# Puzzle_4-Digit_Display_v2_0.net
KiCad netlist of a schematic drawn in EAGLE
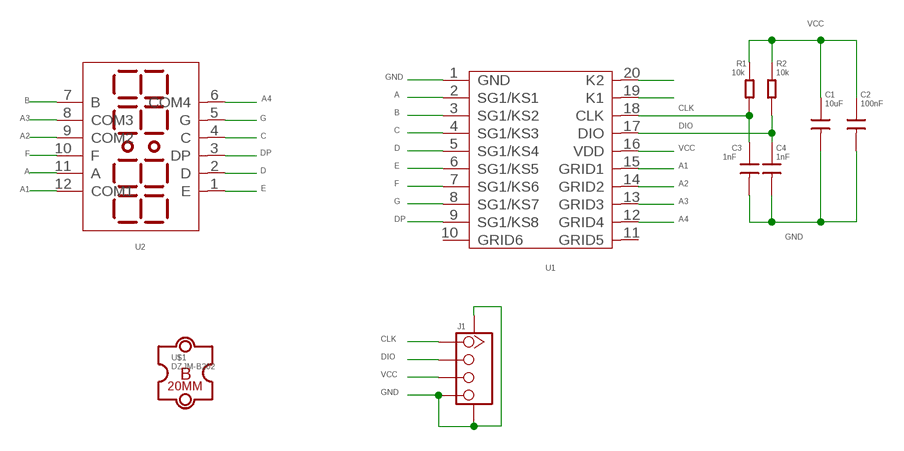
[diagram p0: schematic, sheet 1]

(export (version "E")
  (design (tool "Eeschema 10.0.6"))
  (components
    (comp (ref "C1")
      (value "10uF")
      (footprint "eagle-import:0603")
      (libsource (lib "eagle-import") (part "C-0603"))
    )
    (comp (ref "C2")
      (value "100nF")
      (footprint "eagle-import:0603")
      (libsource (lib "eagle-import") (part "C-0603"))
    )
    (comp (ref "C3")
      (value "1nF")
      (footprint "eagle-import:0603")
      (libsource (lib "eagle-import") (part "C-0603"))
    )
    (comp (ref "C4")
      (value "1nF")
      (footprint "eagle-import:0603")
      (libsource (lib "eagle-import") (part "C-0603"))
    )
    (comp (ref "J1")
      (value "TWIG-4P-2.0-SMD-FEMALE-REINFORCE'90D'")
      (footprint "eagle-import:4P-SMD-2.0-90D")
      (libsource (lib "eagle-import") (part "TWIG-4P-2.0-SMD-FEMALE-REINFORCE'90D'"))
    )
    (comp (ref "R1")
      (value "10k")
      (footprint "eagle-import:0603")
      (libsource (lib "eagle-import") (part "R-0603"))
    )
    (comp (ref "R2")
      (value "10k")
      (footprint "eagle-import:0603")
      (libsource (lib "eagle-import") (part "R-0603"))
    )
    (comp (ref "U$1")
      (value "DZJM-B202")
      (footprint "eagle-import:DZJM-B20-2P")
      (libsource (lib "eagle-import") (part "DZJM-B202"))
    )
    (comp (ref "U1")
      (value "TM1637")
      (footprint "eagle-import:SOP20-10.45")
      (libsource (lib "eagle-import") (part "TM1637"))
    )
    (comp (ref "U2")
      (value "LED-4-BETY-7-SEG")
      (footprint "eagle-import:7-4-BYTE-SEG-2.54-30X14X7.3H")
      (libsource (lib "eagle-import") (part "LED-4-BETY-7-SEG"))
    )
  )
  (nets
    (net (code "1") (name "/A") (class "Default")
      (node (ref "U1") (pin "2") (pinfunction "SG1/KS1_2") (pintype "bidirectional"))
      (node (ref "U2") (pin "11") (pinfunction "A_11") (pintype "bidirectional"))
    )
    (net (code "2") (name "/A1") (class "Default")
      (node (ref "U1") (pin "15") (pinfunction "GRID1_15") (pintype "bidirectional"))
      (node (ref "U2") (pin "12") (pinfunction "COM1_12") (pintype "bidirectional"))
    )
    (net (code "3") (name "/A2") (class "Default")
      (node (ref "U1") (pin "14") (pinfunction "GRID2_14") (pintype "bidirectional"))
      (node (ref "U2") (pin "9") (pinfunction "COM2_9") (pintype "bidirectional"))
    )
    (net (code "4") (name "/A3") (class "Default")
      (node (ref "U1") (pin "13") (pinfunction "GRID3_13") (pintype "bidirectional"))
      (node (ref "U2") (pin "8") (pinfunction "COM3_8") (pintype "bidirectional"))
    )
    (net (code "5") (name "/A4") (class "Default")
      (node (ref "U1") (pin "12") (pinfunction "GRID4_12") (pintype "bidirectional"))
      (node (ref "U2") (pin "6") (pinfunction "COM4_6") (pintype "bidirectional"))
    )
    (net (code "6") (name "/B") (class "Default")
      (node (ref "U1") (pin "3") (pinfunction "SG1/KS2_3") (pintype "bidirectional"))
      (node (ref "U2") (pin "7") (pinfunction "B_7") (pintype "bidirectional"))
    )
    (net (code "7") (name "/C") (class "Default")
      (node (ref "U1") (pin "4") (pinfunction "SG1/KS3_4") (pintype "bidirectional"))
      (node (ref "U2") (pin "4") (pinfunction "C_4") (pintype "bidirectional"))
    )
    (net (code "8") (name "/CLK") (class "Default")
      (node (ref "C3") (pin "1") (pinfunction "1_1") (pintype "passive"))
      (node (ref "J1") (pin "1") (pinfunction "1_1") (pintype "bidirectional"))
      (node (ref "R1") (pin "2") (pinfunction "2_2") (pintype "passive"))
      (node (ref "U1") (pin "18") (pinfunction "CLK_18") (pintype "bidirectional"))
    )
    (net (code "9") (name "/D") (class "Default")
      (node (ref "U1") (pin "5") (pinfunction "SG1/KS4_5") (pintype "bidirectional"))
      (node (ref "U2") (pin "2") (pinfunction "D_2") (pintype "bidirectional"))
    )
    (net (code "10") (name "/DIO") (class "Default")
      (node (ref "C4") (pin "1") (pinfunction "1_1") (pintype "passive"))
      (node (ref "J1") (pin "2") (pinfunction "2_2") (pintype "bidirectional"))
      (node (ref "R2") (pin "2") (pinfunction "2_2") (pintype "passive"))
      (node (ref "U1") (pin "17") (pinfunction "DIO_17") (pintype "bidirectional"))
    )
    (net (code "11") (name "/DP") (class "Default")
      (node (ref "U1") (pin "9") (pinfunction "SG1/KS8_9") (pintype "bidirectional"))
      (node (ref "U2") (pin "3") (pinfunction "DP_3") (pintype "bidirectional"))
    )
    (net (code "12") (name "/E") (class "Default")
      (node (ref "U1") (pin "6") (pinfunction "SG1/KS5_6") (pintype "bidirectional"))
      (node (ref "U2") (pin "1") (pinfunction "E_1") (pintype "bidirectional"))
    )
    (net (code "13") (name "/F") (class "Default")
      (node (ref "U1") (pin "7") (pinfunction "SG1/KS6_7") (pintype "bidirectional"))
      (node (ref "U2") (pin "10") (pinfunction "F_10") (pintype "bidirectional"))
    )
    (net (code "14") (name "/G") (class "Default")
      (node (ref "U1") (pin "8") (pinfunction "SG1/KS7_8") (pintype "bidirectional"))
      (node (ref "U2") (pin "5") (pinfunction "G_5") (pintype "bidirectional"))
    )
    (net (code "15") (name "/GND") (class "Default")
      (node (ref "C1") (pin "2") (pinfunction "2_2") (pintype "passive"))
      (node (ref "C2") (pin "2") (pinfunction "2_2") (pintype "passive"))
      (node (ref "C3") (pin "2") (pinfunction "2_2") (pintype "passive"))
      (node (ref "C4") (pin "2") (pinfunction "2_2") (pintype "passive"))
      (node (ref "J1") (pin "4") (pinfunction "4_4") (pintype "bidirectional"))
      (node (ref "J1") (pin "SS1") (pinfunction "SS1_SS1") (pintype "bidirectional"))
      (node (ref "J1") (pin "SS2") (pinfunction "SS2_SS2") (pintype "bidirectional"))
      (node (ref "U1") (pin "1") (pinfunction "GND_1") (pintype "bidirectional"))
    )
    (net (code "16") (name "/VCC") (class "Default")
      (node (ref "C1") (pin "1") (pinfunction "1_1") (pintype "passive"))
      (node (ref "C2") (pin "1") (pinfunction "1_1") (pintype "passive"))
      (node (ref "J1") (pin "3") (pinfunction "3_3") (pintype "bidirectional"))
      (node (ref "R1") (pin "1") (pinfunction "1_1") (pintype "passive"))
      (node (ref "R2") (pin "1") (pinfunction "1_1") (pintype "passive"))
      (node (ref "U1") (pin "16") (pinfunction "VDD_16") (pintype "bidirectional"))
    )
    (net (code "17") (name "unconnected-(U1-GRID5-Pad11)") (class "Default")
      (node (ref "U1") (pin "11") (pinfunction "GRID5_11") (pintype "bidirectional"))
    )
    (net (code "18") (name "unconnected-(U1-GRID6-Pad10)") (class "Default")
      (node (ref "U1") (pin "10") (pinfunction "GRID6_10") (pintype "bidirectional"))
    )
    (net (code "19") (name "unconnected-(U1-K1-Pad19)") (class "Default")
      (node (ref "U1") (pin "19") (pinfunction "K1_19") (pintype "bidirectional"))
    )
    (net (code "20") (name "unconnected-(U1-K2-Pad20)") (class "Default")
      (node (ref "U1") (pin "20") (pinfunction "K2_20") (pintype "bidirectional"))
    )
  )
)
